# SH2_-_17V_BUCK_CONVERTER.net
KiCad netlist of a schematic drawn in Altium Designer
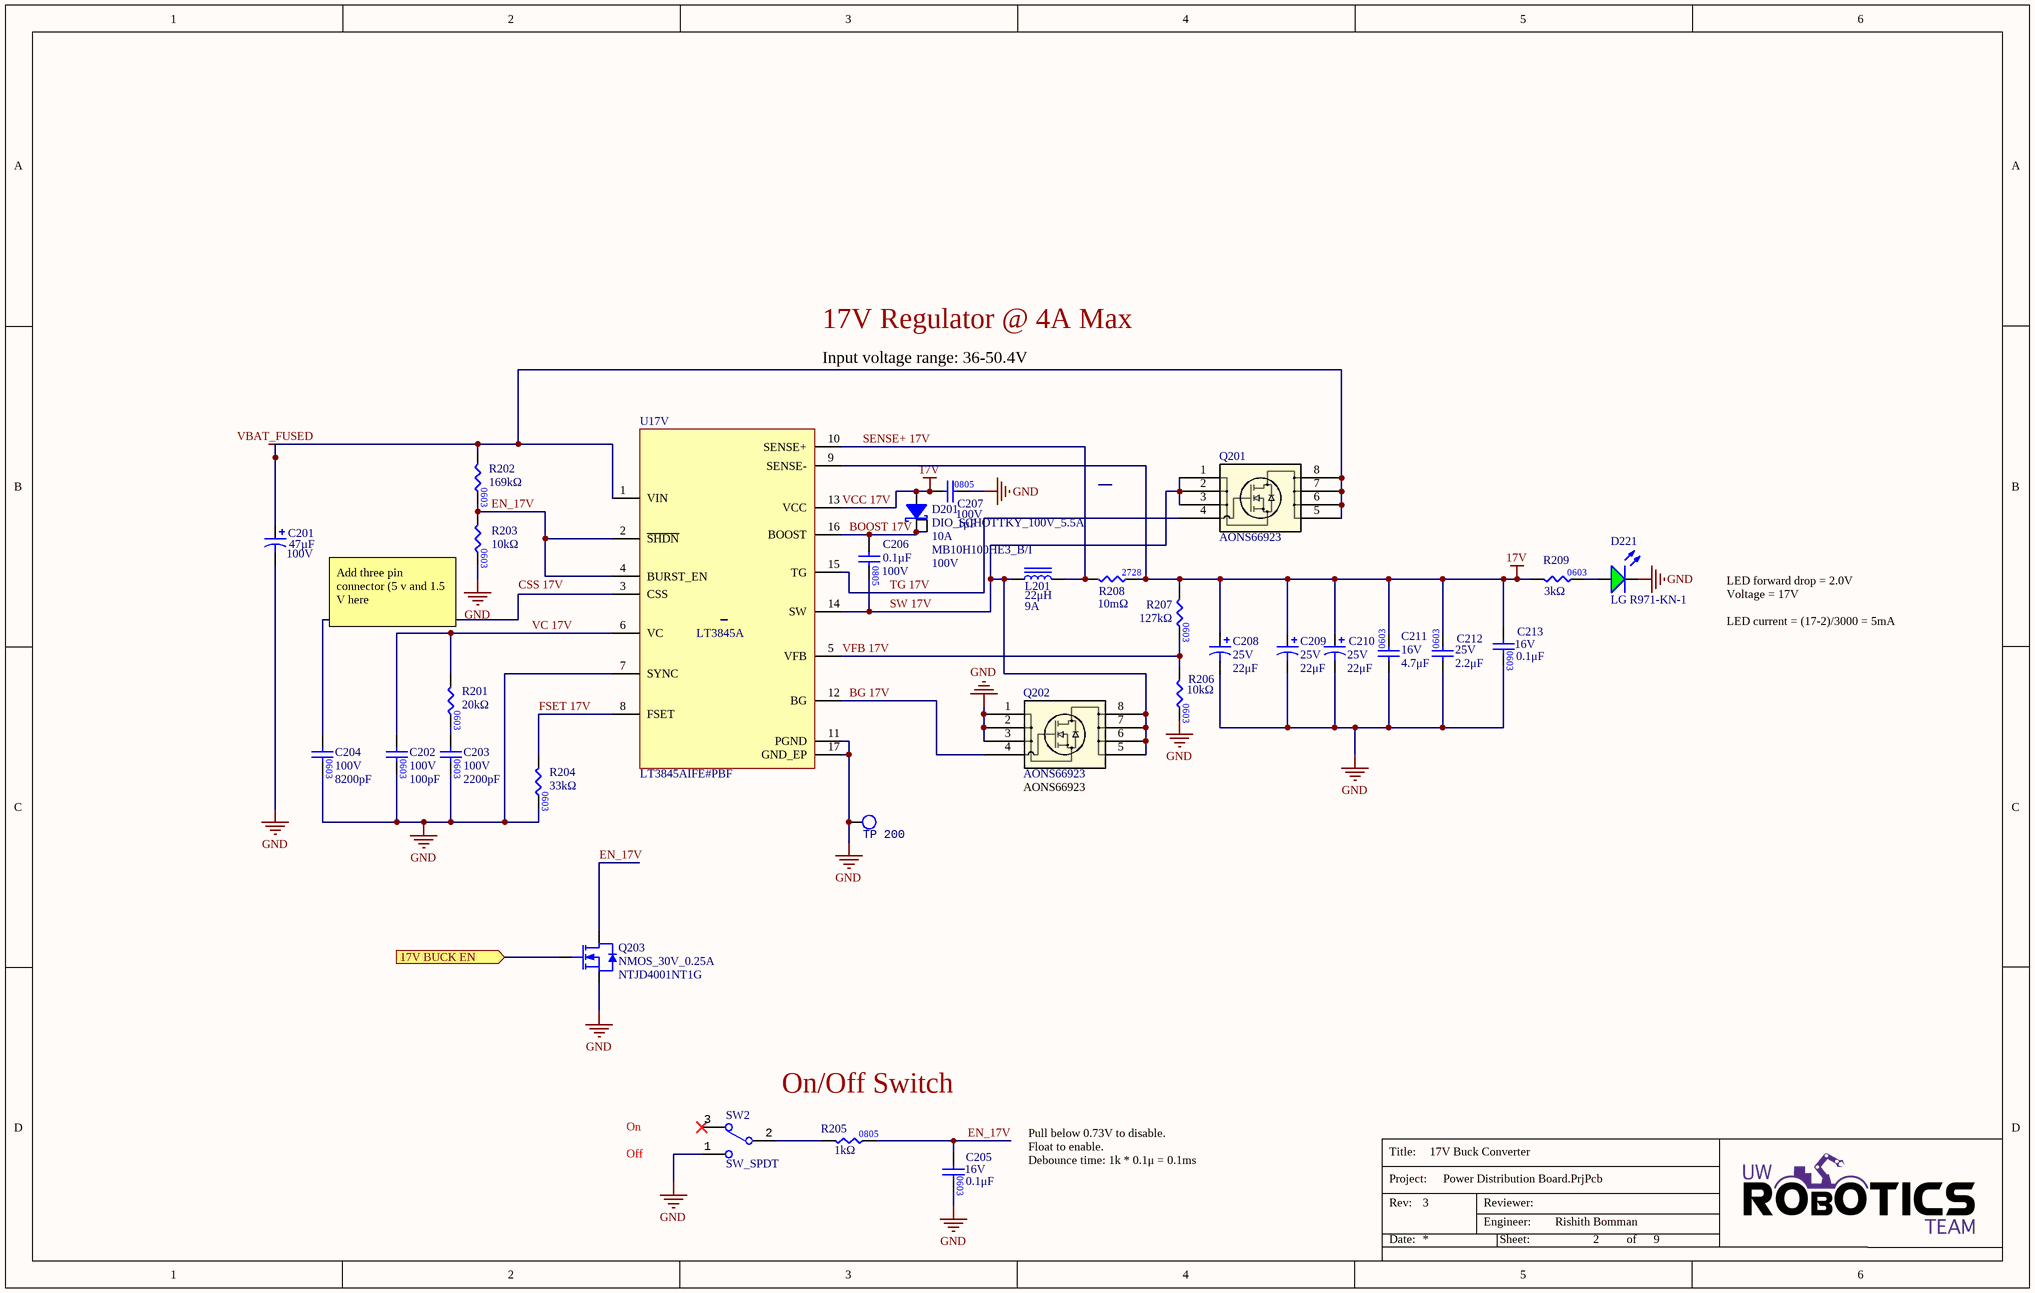
[diagram p0: SH2 - 17V BUCK CONVERTER.SchDoc]

(export (version "E")
  (design (tool "Eeschema 10.0.6"))
  (components
    (comp (ref "C201")
      (value "47µF")
      (footprint "CAP_UCD_10X10_NCH-M")
      (description "CAP ALUM 47UF 20% 100V SMD")
      (fields (field (name "VOLTAGE RATING") "100V") (field (name "Comment") "CAP_47uF_100V_ALUM_1"))
      (libsource (lib "UWRT_Schematic_Library_2020") (part "CAP_47uF_100V_ALUM_1"))
    )
    (comp (ref "C202")
      (value "100pF")
      (footprint "CAP0603")
      (description "CAP CER 100PF 100V C0G/NP0 0603")
      (fields (field (name "VOLTAGE RATING") "100V") (field (name "Comment") "CAP_100pF_100V_0603"))
      (libsource (lib "UWRT_Schematic_Library_2020") (part "CAP_100pF_100V_0603"))
    )
    (comp (ref "C203")
      (value "2200pF")
      (footprint "CAP0603")
      (description "CAP CER 2200PF 100V X7R 0603")
      (fields (field (name "VOLTAGE RATING") "100V") (field (name "Comment") "CAP_2200pF_100V_0603"))
      (libsource (lib "UWRT_Schematic_Library_2020") (part "CAP_2200pF_100V_0603"))
    )
    (comp (ref "C204")
      (value "8200pF")
      (footprint "CAP0603")
      (description "CAP CER 8200PF 100V X7R 0603")
      (fields (field (name "VOLTAGE RATING") "100V") (field (name "Comment") "CAP_8200pF_100V_0603"))
      (libsource (lib "UWRT_Schematic_Library_2020") (part "CAP_8200pF_100V_0603"))
    )
    (comp (ref "C205")
      (value "0.1μF")
      (footprint "CAP0603")
      (description "CAP CER 0.1UF 16V X7R 0603")
      (fields (field (name "VOLTAGE RATING") "16V") (field (name "Comment") "CAP_0.1uF_16V_0603"))
      (libsource (lib "UWRT_Schematic_Library_2020") (part "CAP_0.1uF_16V_0603"))
    )
    (comp (ref "C206")
      (value "0.1µF")
      (footprint "CAP0805")
      (description "CAP CER 0.1UF 100V X7R 0805")
      (fields (field (name "VOLTAGE RATING") "100V") (field (name "Comment") "CAP_0.1uF_100V_0805"))
      (libsource (lib "UWRT_Schematic_Library_2020") (part "CAP_0.1uF_100V_0805"))
    )
    (comp (ref "C207")
      (value "1μF")
      (footprint "CAP2012")
      (description "CAP CER 1UF 100V X7S 0805")
      (fields
        (field (name "LCSC PART #") "C5378")
        (field (name "VOLTAGE RATING") "100V")
        (field (name "Comment") "CAP_1uF_100V_0805")
      )
      (libsource (lib "UWRT_Schematic_Library_2020") (part "CAP_1uF_100V_0805"))
    )
    (comp (ref "C208")
      (value "22μF")
      (footprint "CAP2917")
      (description "CAP TANT 22UF 20% 25V 2917")
      (fields (field (name "VOLTAGE RATING") "25V") (field (name "Comment") "CAP_22uF_25V_TANT"))
      (libsource (lib "UWRT_Schematic_Library_2020") (part "CAP_22uF_25V_TANT"))
    )
    (comp (ref "C209")
      (value "22μF")
      (footprint "CAP2917")
      (description "CAP TANT 22UF 20% 25V 2917")
      (fields (field (name "VOLTAGE RATING") "25V") (field (name "Comment") "CAP_22uF_25V_TANT"))
      (libsource (lib "UWRT_Schematic_Library_2020") (part "CAP_22uF_25V_TANT"))
    )
    (comp (ref "C210")
      (value "22μF")
      (footprint "CAP2917")
      (description "CAP TANT 22UF 20% 25V 2917")
      (fields (field (name "VOLTAGE RATING") "25V") (field (name "Comment") "CAP_22uF_25V_TANT"))
      (libsource (lib "UWRT_Schematic_Library_2020") (part "CAP_22uF_25V_TANT"))
    )
    (comp (ref "C211")
      (value "4.7μF")
      (footprint "CAP0603")
      (description "CAP CER 4.7UF 16V X6S 0603")
      (fields (field (name "VOLTAGE RATING") "16V") (field (name "Comment") "CAP_4.7uF_16V_0603"))
      (libsource (lib "UWRT_Schematic_Library_2020") (part "CAP_4.7uF_16V_0603"))
    )
    (comp (ref "C212")
      (value "2.2μF")
      (footprint "CAP0603")
      (description "CAP CER 2.2UF 25V X5R 0603")
      (fields (field (name "VOLTAGE RATING") "25V") (field (name "Comment") "CAP_2.2uF_25V_0603"))
      (libsource (lib "UWRT_Schematic_Library_2020") (part "CAP_2.2uF_25V_0603"))
    )
    (comp (ref "C213")
      (value "0.1μF")
      (footprint "CAP0603")
      (description "CAP CER 0.1UF 16V X7R 0603")
      (fields (field (name "VOLTAGE RATING") "16V") (field (name "Comment") "CAP_0.1uF_16V_0603"))
      (libsource (lib "UWRT_Schematic_Library_2020") (part "CAP_0.1uF_16V_0603"))
    )
    (comp (ref "D201")
      (value "DIO_SCHOTTKY_100V_5.5A")
      (footprint "D2PAK (TO-263AB)")
      (description "DIODE SCHOTTKY 100V 10A TO263AB")
      (fields
        (field (name "FORWARD CURRENT") "10A")
        (field (name "MANUFACTURER PART NUMBER 1") "MB10H100HE3_B/I")
        (field (name "VR (MAX)") "100V")
      )
      (libsource (lib "UWRT_Schematic_Library_2020") (part "DIO_SCHOTTKY_100V_10A"))
    )
    (comp (ref "D221")
      (value "LED_GREEN")
      (footprint "LED_0805_GREEN")
      (description "LED GREEN DIFFUSED 0805 SMD")
      (fields (field (name "MANUFACTURER PART NUMBER 1") "LG R971-KN-1"))
      (libsource (lib "UWRT_Schematic_Library_2020") (part "LED_GREEN"))
    )
    (comp (ref "L201")
      (value "IND_22uH_9A")
      (footprint "IND_BOURNS_SRP1265")
      (description "22UH 20%  SMD POWER CHOKE")
      (fields (field (name "CURRENT RATING") "9A") (field (name "INDUCTANCE") "22μH"))
      (libsource (lib "UWRT_Schematic_Library_2020") (part "IND_22uH_9A"))
    )
    (comp (ref "Q201")
      (value "AONS66923")
      (footprint "DFN5X6_8L_EP1_P_AOS-L")
      (description "MOSFET N-CH 100V 15A/47A 8DFN")
      (fields (field (name "COPYRIGHT") "Copyright (C) 2022 Ultra Librarian. All rights reserved."))
      (libsource (lib "UWRT_Schematic_Library_2020") (part "NMOS_100V_15/47A_1"))
    )
    (comp (ref "Q202")
      (value "AONS66923")
      (footprint "DFN5X6_8L_EP1_P_AOS-L")
      (description "MOSFET N-CH 100V 15A/47A 8DFN")
      (fields
        (field (name "MANUFACTURER_PART_NUMBER") "AONS66923")
        (field (name "COPYRIGHT") "Copyright (C) 2022 Ultra Librarian. All rights reserved.")
      )
      (libsource (lib "UWRT_Schematic_Library_2020") (part "NMOS_100V_15/47A_1"))
    )
    (comp (ref "Q203")
      (value "NMOS_30V_0.25A")
      (footprint "SOT363")
      (description "MOSFET 2N-CH 30V 0.25A SOT-363")
      (fields (field (name "MANUFACTURER PART NUMBER 1") "NTJD4001NT1G"))
      (libsource (lib "UWRT_Schematic_Library_2020") (part "NMOS_30V_0.25A"))
    )
    (comp (ref "R201")
      (value "20kΩ")
      (footprint "RES0603")
      (description "RES 20K OHM 1% 1/10W 0603")
      (fields (field (name "Comment") "RES_20kΩ_0603_1%"))
      (libsource (lib "UWRT_Schematic_Library_2020") (part "RES_20kΩ_0603_1%"))
    )
    (comp (ref "R202")
      (value "169kΩ")
      (footprint "RES0603")
      (description "RES 169K OHM 1% 1/10W 0603")
      (fields (field (name "Comment") "RES_169kΩ_0603_1%"))
      (libsource (lib "UWRT_Schematic_Library_2020") (part "RES_169kΩ_0603_1%"))
    )
    (comp (ref "R203")
      (value "10kΩ")
      (footprint "RES0603")
      (description "RES 10K OHM 5% 1/10W 0603")
      (fields (field (name "Comment") "RES_10kΩ_0603_5%"))
      (libsource (lib "UWRT_Schematic_Library_2020") (part "RES_10kΩ_0603_5%"))
    )
    (comp (ref "R204")
      (value "33kΩ")
      (footprint "RES0603")
      (description "RES 33K OHM 5% 1/10W 0603")
      (fields (field (name "Comment") "RES_33kΩ_0603_5%"))
      (libsource (lib "UWRT_Schematic_Library_2020") (part "RES_33kΩ_0603_5%"))
    )
    (comp (ref "R205")
      (value "1kΩ")
      (footprint "RES0805")
      (description "RES 1K OHM 1% 1/8W 0805")
      (fields (field (name "LCSC PART #") "C17513") (field (name "Comment") "RES_1kΩ_0805_1%_1"))
      (libsource (lib "UWRT_Schematic_Library_2020") (part "RES_1kΩ_0805_1%_1"))
    )
    (comp (ref "R206")
      (value "10kΩ")
      (footprint "RES0603")
      (description "RES 10K OHM 5% 1/10W 0603")
      (fields (field (name "Comment") "RES_10kΩ_0603_5%"))
      (libsource (lib "UWRT_Schematic_Library_2020") (part "RES_10kΩ_0603_5%"))
    )
    (comp (ref "R207")
      (value "127kΩ")
      (footprint "RES0603")
      (description "RES 127K OHM 1% 1/10W 0603")
      (fields (field (name "Comment") "RES_127kΩ_0603_1%"))
      (libsource (lib "UWRT_Schematic_Library_2020") (part "RES_127kΩ_0603_1%"))
    )
    (comp (ref "R208")
      (value "10mΩ")
      (footprint "STAC-CSS2725-099H_V")
      (description "RES 10mOHM 1% 4W 2728")
      (fields (field (name "Comment") "RES_10mΩ_2728_1%"))
      (libsource (lib "UWRT_Schematic_Library_2020") (part "RES_10mΩ_2728_1%"))
    )
    (comp (ref "R209")
      (value "3kΩ")
      (footprint "RES0603")
      (description "RES 3K OHM 1% 1/10W 0603")
      (fields (field (name "Comment") "RES_3kΩ_0603_1%"))
      (libsource (lib "UWRT_Schematic_Library_2020") (part "RES_3kΩ_0603_1%"))
    )
    (comp (ref "SW2")
      (value "SW_SPDT")
      (footprint "100SP1T1B4M2QE")
      (description "SWITCH TOGGLE SPDT 5A 120V")
      (libsource (lib "UWRT_Schematic_Library_2020") (part "SW_SPDT"))
    )
    (comp (ref "TP 200")
      (value "TESTPOINT_LOOP")
      (footprint "TESTPOINT_LOOP")
      (description "TESTPOINT THRUHOLE")
      (libsource (lib "UWRT_Schematic_Library_2020") (part "TESTPOINT_LOOP"))
    )
    (comp (ref "U17V")
      (value "BUCK_LT3845A")
      (footprint "LT3845AIFE#PBF")
      (description "IC REG CTRLR BUCK 16TSSOP")
      (fields (field (name "MANUFACTURER PART NUMBER 1") "LT3845AIFE#PBF"))
      (libsource (lib "UWRT_Schematic_Library_2020") (part "BUCK_LT3845A"))
    )
  )
  (nets
    (net (code "1") (name "/17V BUCK EN") (class "Default")
      (node (ref "Q203") (pin "1") (pinfunction "GATE_1") (pintype "passive"))
    )
    (net (code "2") (name "/BG 17V") (class "Default")
      (node (ref "Q202") (pin "4") (pinfunction "4_4") (pintype "passive"))
      (node (ref "U17V") (pin "12") (pinfunction "BG_12") (pintype "passive"))
    )
    (net (code "3") (name "/BOOST 17V") (class "Default")
      (node (ref "C206") (pin "1") (pinfunction "1_1") (pintype "passive"))
      (node (ref "D201") (pin "1") (pinfunction "Cathode_1") (pintype "passive"))
      (node (ref "D201") (pin "3") (pinfunction "Heatsink_(K)_3") (pintype "passive"))
      (node (ref "U17V") (pin "16") (pinfunction "BOOST_16") (pintype "passive"))
    )
    (net (code "5") (name "/EN_17V") (class "Default")
      (node (ref "C205") (pin "1") (pinfunction "1_1") (pintype "passive"))
      (node (ref "Q203") (pin "3") (pinfunction "DRAIN_3") (pintype "passive"))
      (node (ref "R202") (pin "2") (pinfunction "2_2") (pintype "passive"))
      (node (ref "R203") (pin "1") (pinfunction "1_1") (pintype "passive"))
      (node (ref "R205") (pin "2") (pinfunction "2_2") (pintype "passive"))
      (node (ref "U17V") (pin "2") (pinfunction "~{SHDN}_2") (pintype "passive"))
      (node (ref "U17V") (pin "4") (pinfunction "BURST_EN_4") (pintype "passive"))
    )
    (net (code "6") (name "/FSET 17V") (class "Default")
      (node (ref "R204") (pin "1") (pinfunction "1_1") (pintype "passive"))
      (node (ref "U17V") (pin "8") (pinfunction "FSET_8") (pintype "passive"))
    )
    (net (code "7") (name "/SENSE+ 17V") (class "Default")
      (node (ref "L201") (pin "2") (pinfunction "2_2") (pintype "passive"))
      (node (ref "R208") (pin "1") (pinfunction "1_1") (pintype "passive"))
      (node (ref "U17V") (pin "10") (pinfunction "SENSE+_10") (pintype "passive"))
    )
    (net (code "8") (name "/SW 17V") (class "Default")
      (node (ref "C206") (pin "2") (pinfunction "2_2") (pintype "passive"))
      (node (ref "L201") (pin "1") (pinfunction "1_1") (pintype "passive"))
      (node (ref "Q201") (pin "1") (pinfunction "1_1") (pintype "passive"))
      (node (ref "Q201") (pin "2") (pinfunction "2_2") (pintype "passive"))
      (node (ref "Q201") (pin "3") (pinfunction "3_3") (pintype "passive"))
      (node (ref "Q202") (pin "5") (pinfunction "5_5") (pintype "passive"))
      (node (ref "Q202") (pin "6") (pinfunction "6_6") (pintype "passive"))
      (node (ref "Q202") (pin "7") (pinfunction "7_7") (pintype "passive"))
      (node (ref "Q202") (pin "8") (pinfunction "8_8") (pintype "passive"))
      (node (ref "U17V") (pin "14") (pinfunction "SW_14") (pintype "passive"))
    )
    (net (code "9") (name "/TG 17V") (class "Default")
      (node (ref "Q201") (pin "4") (pinfunction "4_4") (pintype "passive"))
      (node (ref "U17V") (pin "15") (pinfunction "TG_15") (pintype "passive"))
    )
    (net (code "10") (name "/VC 17V") (class "Default")
      (node (ref "C202") (pin "1") (pinfunction "1_1") (pintype "passive"))
      (node (ref "R201") (pin "1") (pinfunction "1_1") (pintype "passive"))
      (node (ref "U17V") (pin "6") (pinfunction "VC_6") (pintype "passive"))
    )
    (net (code "11") (name "/VFB 17V") (class "Default")
      (node (ref "R206") (pin "1") (pinfunction "1_1") (pintype "passive"))
      (node (ref "R207") (pin "2") (pinfunction "2_2") (pintype "passive"))
      (node (ref "U17V") (pin "5") (pinfunction "VFB_5") (pintype "passive"))
    )
    (net (code "12") (name "17V") (class "Default")
      (node (ref "C207") (pin "1") (pinfunction "1_1") (pintype "passive"))
      (node (ref "C208") (pin "1") (pinfunction "1_1") (pintype "passive"))
      (node (ref "C209") (pin "1") (pinfunction "1_1") (pintype "passive"))
      (node (ref "C210") (pin "1") (pinfunction "1_1") (pintype "passive"))
      (node (ref "C211") (pin "2") (pinfunction "2_2") (pintype "passive"))
      (node (ref "C212") (pin "2") (pinfunction "2_2") (pintype "passive"))
      (node (ref "C213") (pin "1") (pinfunction "1_1") (pintype "passive"))
      (node (ref "D201") (pin "2") (pinfunction "Anode_2") (pintype "passive"))
      (node (ref "R207") (pin "1") (pinfunction "1_1") (pintype "passive"))
      (node (ref "R208") (pin "2") (pinfunction "2_2") (pintype "passive"))
      (node (ref "R209") (pin "1") (pinfunction "1_1") (pintype "passive"))
      (node (ref "U17V") (pin "13") (pinfunction "VCC_13") (pintype "passive"))
      (node (ref "U17V") (pin "9") (pinfunction "SENSE-_9") (pintype "passive"))
    )
    (net (code "13") (name "GND") (class "Default")
      (node (ref "C201") (pin "2") (pinfunction "2_2") (pintype "passive"))
      (node (ref "C202") (pin "2") (pinfunction "2_2") (pintype "passive"))
      (node (ref "C203") (pin "2") (pinfunction "2_2") (pintype "passive"))
      (node (ref "C204") (pin "2") (pinfunction "2_2") (pintype "passive"))
      (node (ref "C205") (pin "2") (pinfunction "2_2") (pintype "passive"))
      (node (ref "C207") (pin "2") (pinfunction "2_2") (pintype "passive"))
      (node (ref "C208") (pin "2") (pinfunction "2_2") (pintype "passive"))
      (node (ref "C209") (pin "2") (pinfunction "2_2") (pintype "passive"))
      (node (ref "C210") (pin "2") (pinfunction "2_2") (pintype "passive"))
      (node (ref "C211") (pin "1") (pinfunction "1_1") (pintype "passive"))
      (node (ref "C212") (pin "1") (pinfunction "1_1") (pintype "passive"))
      (node (ref "C213") (pin "2") (pinfunction "2_2") (pintype "passive"))
      (node (ref "D221") (pin "2") (pinfunction "K_2") (pintype "passive"))
      (node (ref "Q202") (pin "1") (pinfunction "1_1") (pintype "passive"))
      (node (ref "Q202") (pin "2") (pinfunction "2_2") (pintype "passive"))
      (node (ref "Q202") (pin "3") (pinfunction "3_3") (pintype "passive"))
      (node (ref "Q203") (pin "2") (pinfunction "SOURCE_2") (pintype "passive"))
      (node (ref "R203") (pin "2") (pinfunction "2_2") (pintype "passive"))
      (node (ref "R204") (pin "2") (pinfunction "2_2") (pintype "passive"))
      (node (ref "R206") (pin "2") (pinfunction "2_2") (pintype "passive"))
      (node (ref "SW2") (pin "1") (pinfunction "1_1") (pintype "passive"))
      (node (ref "TP 200") (pin "1") (pintype "passive"))
      (node (ref "U17V") (pin "11") (pinfunction "PGND_11") (pintype "power_in"))
      (node (ref "U17V") (pin "17") (pinfunction "GND_EP_17") (pintype "power_in"))
      (node (ref "U17V") (pin "7") (pinfunction "SYNC_7") (pintype "passive"))
    )
    (net (code "14") (name "Net-(C203-Pad1)") (class "Default")
      (node (ref "C203") (pin "1") (pinfunction "1_1") (pintype "passive"))
      (node (ref "R201") (pin "2") (pinfunction "2_2") (pintype "passive"))
    )
    (net (code "15") (name "Net-(D221-A)") (class "Default")
      (node (ref "D221") (pin "1") (pinfunction "A_1") (pintype "passive"))
      (node (ref "R209") (pin "2") (pinfunction "2_2") (pintype "passive"))
    )
    (net (code "16") (name "Net-(R205-Pad1)") (class "Default")
      (node (ref "R205") (pin "1") (pinfunction "1_1") (pintype "passive"))
      (node (ref "SW2") (pin "2") (pinfunction "2_2") (pintype "passive"))
    )
    (net (code "17") (name "Net-(U17V-CSS)") (class "Default")
      (node (ref "C204") (pin "1") (pinfunction "1_1") (pintype "passive"))
      (node (ref "U17V") (pin "3") (pinfunction "CSS_3") (pintype "passive"))
    )
    (net (code "18") (name "VBAT_FUSED") (class "Default")
      (node (ref "C201") (pin "1") (pinfunction "1_1") (pintype "passive"))
      (node (ref "Q201") (pin "5") (pinfunction "5_5") (pintype "passive"))
      (node (ref "Q201") (pin "6") (pinfunction "6_6") (pintype "passive"))
      (node (ref "Q201") (pin "7") (pinfunction "7_7") (pintype "passive"))
      (node (ref "Q201") (pin "8") (pinfunction "8_8") (pintype "passive"))
      (node (ref "R202") (pin "1") (pinfunction "1_1") (pintype "passive"))
      (node (ref "U17V") (pin "1") (pinfunction "VIN_1") (pintype "passive"))
    )
    (net (code "19") (name "unconnected-(SW2-Pad3)") (class "Default")
      (node (ref "SW2") (pin "3") (pinfunction "3_3") (pintype "passive+no_connect"))
    )
  )
)
